# ov2640.net
KiCad netlist of a schematic drawn in Altium Designer
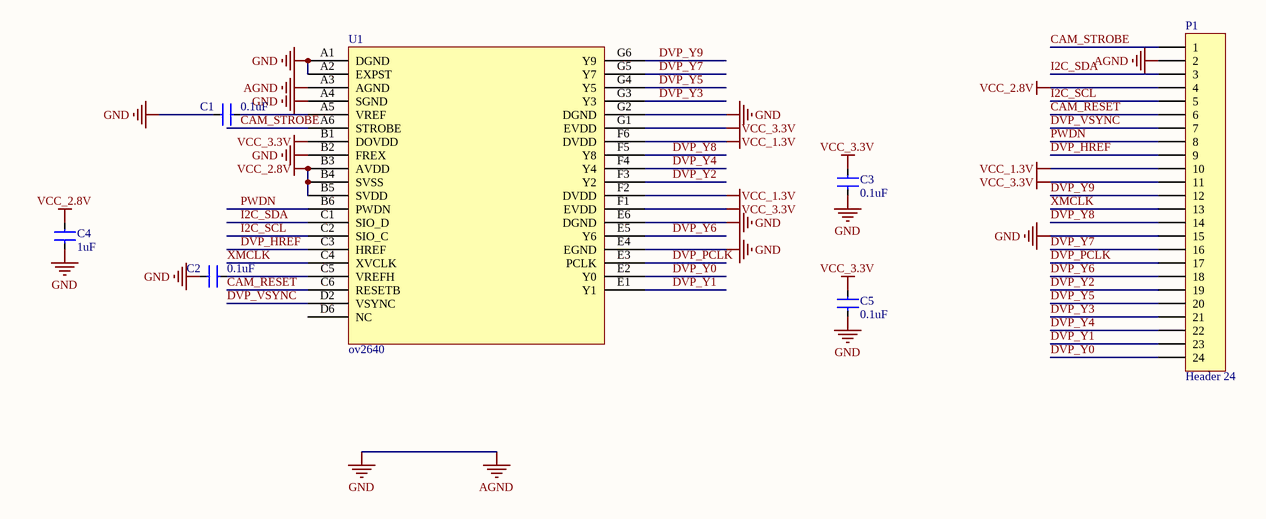
[diagram p0: ov2640.SchDoc]

(export (version "E")
  (design (tool "Eeschema 10.0.6"))
  (components
    (comp (ref "C1")
      (value "0.1uF")
      (footprint "0402C")
      (description "CCX85-103")
      (libsource (lib "无极性电容") (part "0.01UF"))
    )
    (comp (ref "C2")
      (value "0.1uF")
      (footprint "0402C")
      (description "CCX85-103")
      (libsource (lib "无极性电容") (part "0.01UF"))
    )
    (comp (ref "C3")
      (value "0.1uF")
      (footprint "0402C")
      (description "CCX85-103")
      (libsource (lib "无极性电容") (part "0.01UF"))
    )
    (comp (ref "C4")
      (value "1uF")
      (footprint "0402C")
      (description "CCX85-103")
      (libsource (lib "无极性电容") (part "0.01UF"))
    )
    (comp (ref "C5")
      (value "0.1uF")
      (footprint "0402C")
      (description "CCX85-103")
      (libsource (lib "无极性电容") (part "0.01UF"))
    )
    (comp (ref "P1")
      (value "Header 24")
      (footprint "FPC24PIN_0.5MM")
      (description "Header, 24-Pin")
      (fields (field (name "PUBLISHER") "Altium Limited"))
      (libsource (lib "Miscellaneous Connectors") (part "Header 24"))
    )
    (comp (ref "U1")
      (value "ov2640")
      (footprint "BGA100P9X9-81A")
      (libsource (lib "Schlib_20110825") (part "ov2640"))
    )
  )
  (nets
    (net (code "1") (name "/CAM_RESET") (class "Default")
      (node (ref "P1") (pin "6") (pinfunction "6_6") (pintype "passive"))
      (node (ref "U1") (pin "C6") (pinfunction "RESETB_C6") (pintype "passive"))
    )
    (net (code "2") (name "/CAM_STROBE") (class "Default")
      (node (ref "P1") (pin "1") (pinfunction "1_1") (pintype "passive"))
      (node (ref "U1") (pin "A6") (pinfunction "STROBE_A6") (pintype "passive"))
    )
    (net (code "3") (name "/DVP_HREF") (class "Default")
      (node (ref "P1") (pin "9") (pinfunction "9_9") (pintype "passive"))
      (node (ref "U1") (pin "C3") (pinfunction "HREF_C3") (pintype "passive"))
    )
    (net (code "4") (name "/DVP_PCLK") (class "Default")
      (node (ref "P1") (pin "17") (pinfunction "17_17") (pintype "passive"))
      (node (ref "U1") (pin "E3") (pinfunction "PCLK_E3") (pintype "passive"))
    )
    (net (code "5") (name "/DVP_VSYNC") (class "Default")
      (node (ref "P1") (pin "7") (pinfunction "7_7") (pintype "passive"))
      (node (ref "U1") (pin "D2") (pinfunction "VSYNC_D2") (pintype "passive"))
    )
    (net (code "6") (name "/DVP_Y0") (class "Default")
      (node (ref "P1") (pin "24") (pinfunction "24_24") (pintype "passive"))
      (node (ref "U1") (pin "E2") (pinfunction "Y0_E2") (pintype "passive"))
    )
    (net (code "7") (name "/DVP_Y1") (class "Default")
      (node (ref "P1") (pin "23") (pinfunction "23_23") (pintype "passive"))
      (node (ref "U1") (pin "E1") (pinfunction "Y1_E1") (pintype "passive"))
    )
    (net (code "8") (name "/DVP_Y2") (class "Default")
      (node (ref "P1") (pin "19") (pinfunction "19_19") (pintype "passive"))
      (node (ref "U1") (pin "F3") (pinfunction "Y2_F3") (pintype "passive"))
    )
    (net (code "9") (name "/DVP_Y3") (class "Default")
      (node (ref "P1") (pin "21") (pinfunction "21_21") (pintype "passive"))
      (node (ref "U1") (pin "G3") (pinfunction "Y3_G3") (pintype "passive"))
    )
    (net (code "10") (name "/DVP_Y4") (class "Default")
      (node (ref "P1") (pin "22") (pinfunction "22_22") (pintype "passive"))
      (node (ref "U1") (pin "F4") (pinfunction "Y4_F4") (pintype "passive"))
    )
    (net (code "11") (name "/DVP_Y5") (class "Default")
      (node (ref "P1") (pin "20") (pinfunction "20_20") (pintype "passive"))
      (node (ref "U1") (pin "G4") (pinfunction "Y5_G4") (pintype "passive"))
    )
    (net (code "12") (name "/DVP_Y6") (class "Default")
      (node (ref "P1") (pin "18") (pinfunction "18_18") (pintype "passive"))
      (node (ref "U1") (pin "E5") (pinfunction "Y6_E5") (pintype "passive"))
    )
    (net (code "13") (name "/DVP_Y7") (class "Default")
      (node (ref "P1") (pin "16") (pinfunction "16_16") (pintype "passive"))
      (node (ref "U1") (pin "G5") (pinfunction "Y7_G5") (pintype "passive"))
    )
    (net (code "14") (name "/DVP_Y8") (class "Default")
      (node (ref "P1") (pin "14") (pinfunction "14_14") (pintype "passive"))
      (node (ref "U1") (pin "F5") (pinfunction "Y8_F5") (pintype "passive"))
    )
    (net (code "15") (name "/DVP_Y9") (class "Default")
      (node (ref "P1") (pin "12") (pinfunction "12_12") (pintype "passive"))
      (node (ref "U1") (pin "G6") (pinfunction "Y9_G6") (pintype "passive"))
    )
    (net (code "16") (name "/I2C_SCL") (class "Default")
      (node (ref "P1") (pin "5") (pinfunction "5_5") (pintype "passive"))
      (node (ref "U1") (pin "C2") (pinfunction "SIO_C_C2") (pintype "passive"))
    )
    (net (code "17") (name "/I2C_SDA") (class "Default")
      (node (ref "P1") (pin "3") (pinfunction "3_3") (pintype "passive"))
      (node (ref "U1") (pin "C1") (pinfunction "SIO_D_C1") (pintype "passive"))
    )
    (net (code "18") (name "/PWDN") (class "Default")
      (node (ref "P1") (pin "8") (pinfunction "8_8") (pintype "passive"))
      (node (ref "U1") (pin "B6") (pinfunction "PWDN_B6") (pintype "passive"))
    )
    (net (code "19") (name "/XMCLK") (class "Default")
      (node (ref "P1") (pin "13") (pinfunction "13_13") (pintype "passive"))
      (node (ref "U1") (pin "C4") (pinfunction "XVCLK_C4") (pintype "passive"))
    )
    (net (code "20") (name "AGND") (class "Default")
      (node (ref "C1") (pin "1") (pinfunction "1_1") (pintype "passive"))
      (node (ref "C2") (pin "1") (pinfunction "1_1") (pintype "passive"))
      (node (ref "C3") (pin "1") (pinfunction "1_1") (pintype "passive"))
      (node (ref "C4") (pin "1") (pinfunction "1_1") (pintype "passive"))
      (node (ref "C5") (pin "1") (pinfunction "1_1") (pintype "passive"))
      (node (ref "P1") (pin "15") (pinfunction "15_15") (pintype "passive"))
      (node (ref "P1") (pin "2") (pinfunction "2_2") (pintype "passive"))
      (node (ref "U1") (pin "A1") (pinfunction "DGND_A1") (pintype "passive"))
      (node (ref "U1") (pin "A2") (pinfunction "EXPST_A2") (pintype "passive"))
      (node (ref "U1") (pin "A3") (pinfunction "AGND_A3") (pintype "passive"))
      (node (ref "U1") (pin "A4") (pinfunction "SGND_A4") (pintype "passive"))
      (node (ref "U1") (pin "B2") (pinfunction "FREX_B2") (pintype "passive"))
      (node (ref "U1") (pin "E4") (pinfunction "EGND_E4") (pintype "passive"))
      (node (ref "U1") (pin "E6") (pinfunction "DGND_E6") (pintype "passive"))
      (node (ref "U1") (pin "G2") (pinfunction "DGND_G2") (pintype "passive"))
    )
    (net (code "21") (name "Net-(U1-VREF)") (class "Default")
      (node (ref "C1") (pin "2") (pinfunction "2_2") (pintype "passive"))
      (node (ref "U1") (pin "A5") (pinfunction "VREF_A5") (pintype "passive"))
    )
    (net (code "22") (name "Net-(U1-VREFH)") (class "Default")
      (node (ref "C2") (pin "2") (pinfunction "2_2") (pintype "passive"))
      (node (ref "U1") (pin "C5") (pinfunction "VREFH_C5") (pintype "passive"))
    )
    (net (code "23") (name "VCC_1.3V") (class "Default")
      (node (ref "P1") (pin "10") (pinfunction "10_10") (pintype "passive"))
      (node (ref "U1") (pin "F2") (pinfunction "DVDD_F2") (pintype "passive"))
      (node (ref "U1") (pin "F6") (pinfunction "DVDD_F6") (pintype "passive"))
    )
    (net (code "24") (name "VCC_2.8V") (class "Default")
      (node (ref "C4") (pin "2") (pinfunction "2_2") (pintype "passive"))
      (node (ref "P1") (pin "4") (pinfunction "4_4") (pintype "passive"))
      (node (ref "U1") (pin "B3") (pinfunction "AVDD_B3") (pintype "passive"))
      (node (ref "U1") (pin "B4") (pinfunction "SVSS_B4") (pintype "passive"))
      (node (ref "U1") (pin "B5") (pinfunction "SVDD_B5") (pintype "passive"))
    )
    (net (code "25") (name "VCC_3.3V") (class "Default")
      (node (ref "C3") (pin "2") (pinfunction "2_2") (pintype "passive"))
      (node (ref "C5") (pin "2") (pinfunction "2_2") (pintype "passive"))
      (node (ref "P1") (pin "11") (pinfunction "11_11") (pintype "passive"))
      (node (ref "U1") (pin "B1") (pinfunction "DOVDD_B1") (pintype "passive"))
      (node (ref "U1") (pin "F1") (pinfunction "EVDD_F1") (pintype "passive"))
      (node (ref "U1") (pin "G1") (pinfunction "EVDD_G1") (pintype "passive"))
    )
    (net (code "26") (name "unconnected-(U1-NC-PadD6)") (class "Default")
      (node (ref "U1") (pin "D6") (pinfunction "NC_D6") (pintype "passive"))
    )
  )
)
